# BMS.net
KiCad netlist of a schematic drawn in EAGLE
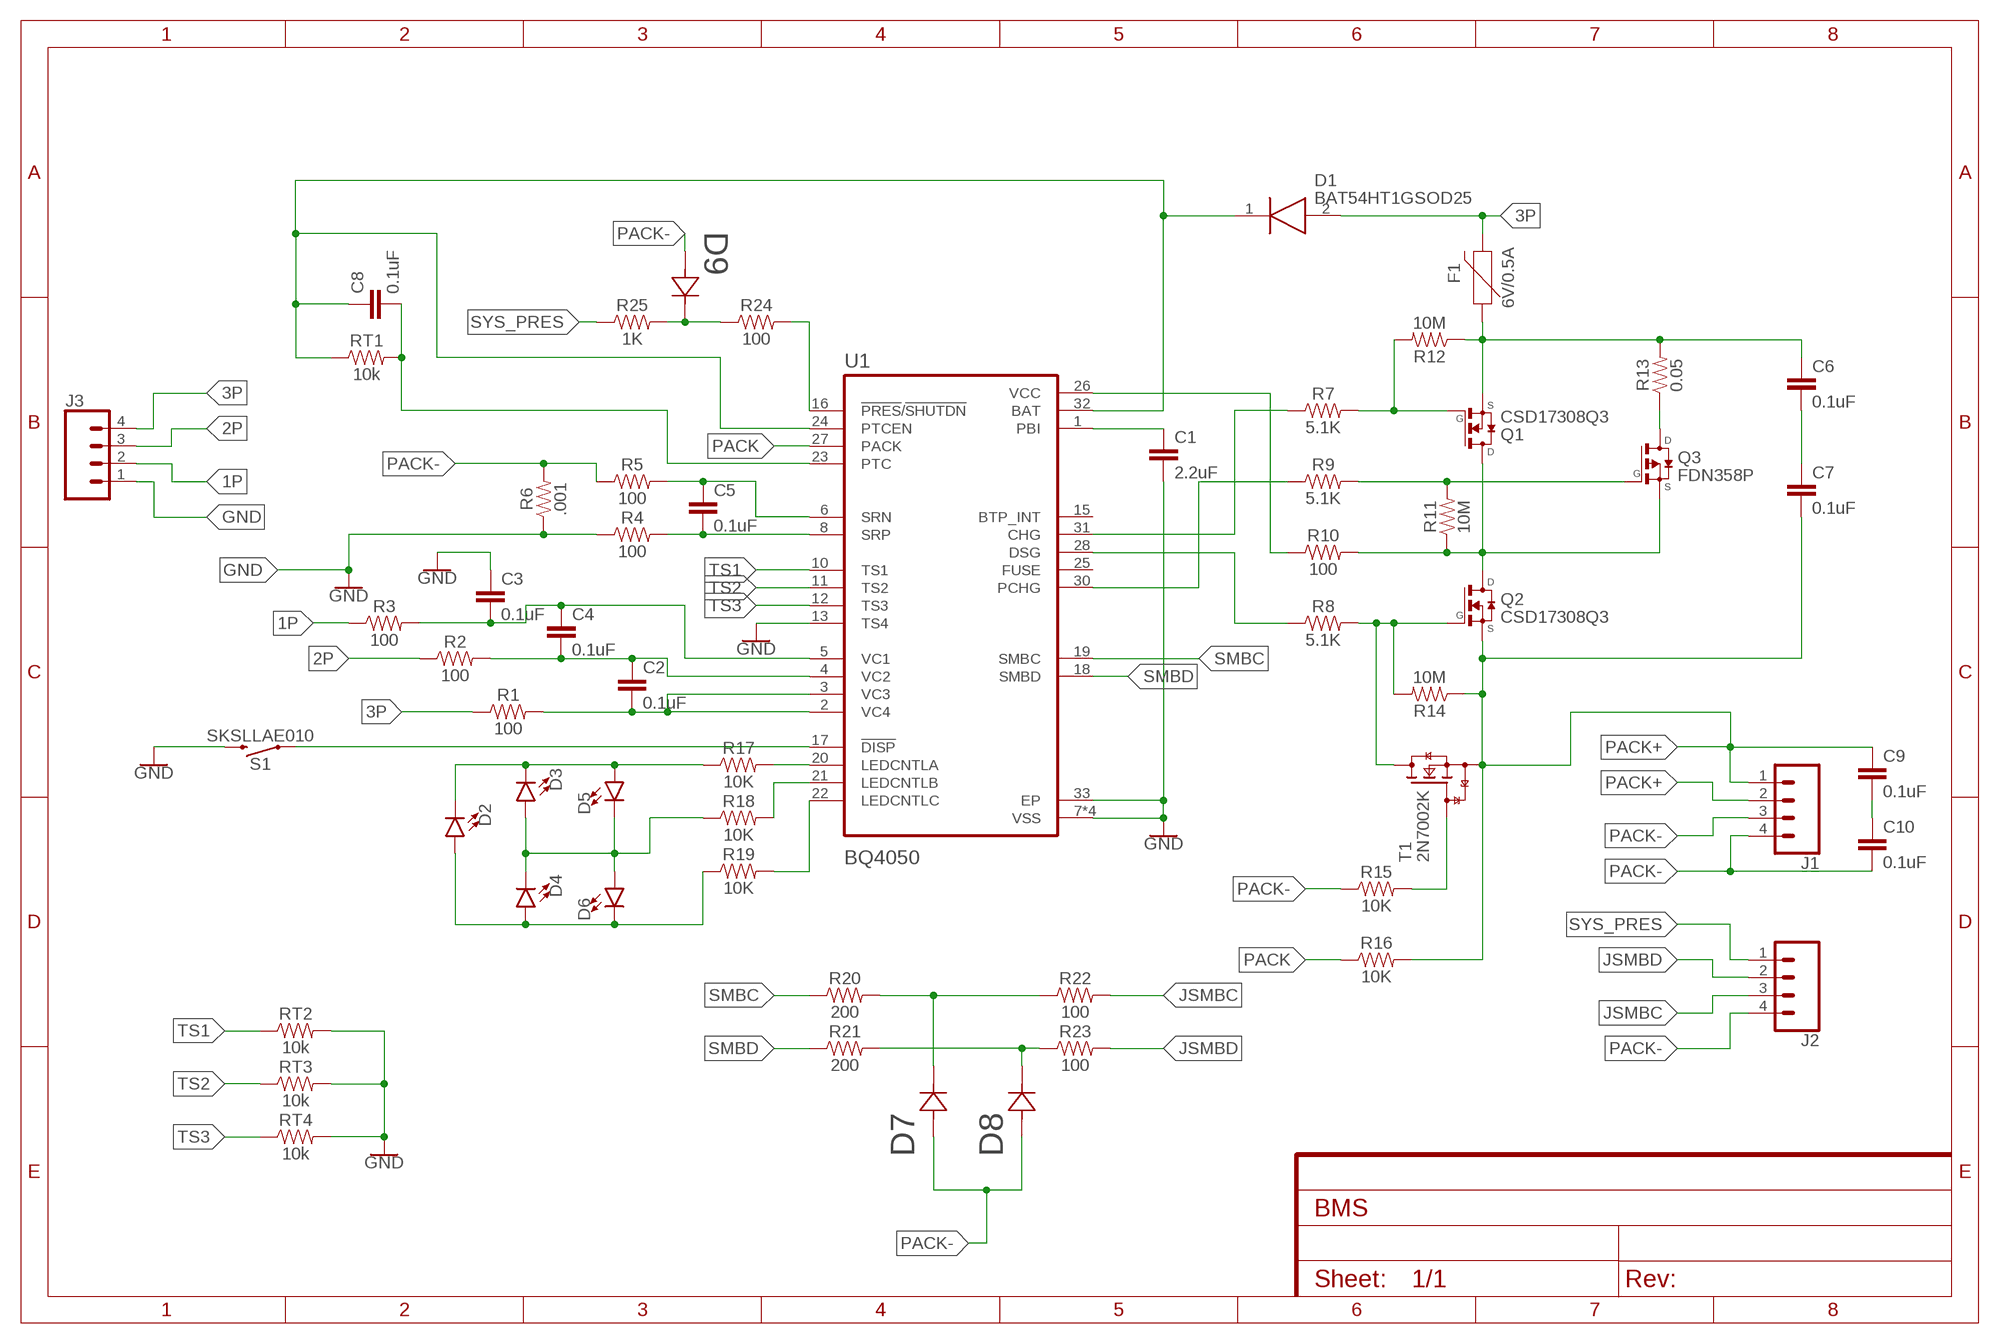
[diagram p0: schematic, sheet 1]

(export (version "E")
  (design (tool "Eeschema 10.0.6"))
  (components
    (comp (ref "C1")
      (value "2.2uF")
      (footprint "eagle-import:0402-CAP")
      (libsource (lib "eagle-import") (part "2.2UF-CERCAP-07888"))
    )
    (comp (ref "C2")
      (value "0.1uF")
      (footprint "eagle-import:0402")
      (libsource (lib "eagle-import") (part "0.1UF-0402-16V-10%"))
    )
    (comp (ref "C3")
      (value "0.1uF")
      (footprint "eagle-import:0402")
      (libsource (lib "eagle-import") (part "0.1UF-0402-16V-10%"))
    )
    (comp (ref "C4")
      (value "0.1uF")
      (footprint "eagle-import:0402")
      (libsource (lib "eagle-import") (part "0.1UF-0402-16V-10%"))
    )
    (comp (ref "C5")
      (value "0.1uF")
      (footprint "eagle-import:0402")
      (libsource (lib "eagle-import") (part "0.1UF-0402-16V-10%"))
    )
    (comp (ref "C6")
      (value "0.1uF")
      (footprint "eagle-import:0402")
      (libsource (lib "eagle-import") (part "0.1UF-0402-16V-10%"))
    )
    (comp (ref "C7")
      (value "0.1uF")
      (footprint "eagle-import:0402")
      (libsource (lib "eagle-import") (part "0.1UF-0402-16V-10%"))
    )
    (comp (ref "C8")
      (value "0.1uF")
      (footprint "eagle-import:0402")
      (libsource (lib "eagle-import") (part "0.1UF-0402-16V-10%"))
    )
    (comp (ref "C9")
      (value "0.1uF")
      (footprint "eagle-import:0402")
      (libsource (lib "eagle-import") (part "0.1UF-0402-16V-10%"))
    )
    (comp (ref "C10")
      (value "0.1uF")
      (footprint "eagle-import:0402")
      (libsource (lib "eagle-import") (part "0.1UF-0402-16V-10%"))
    )
    (comp (ref "D1")
      (value "BAT54HT1GSOD25")
      (footprint "eagle-import:SOD2512X100")
      (libsource (lib "eagle-import") (part "BAT54HT1GSOD25"))
    )
    (comp (ref "D2")
      (value "LTW-S272TLA-1175391")
      (footprint "eagle-import:LTW-S272TLA-1175391")
      (libsource (lib "eagle-import") (part "LTW-S272TLA-1175391"))
    )
    (comp (ref "D3")
      (value "LTW-S272TLA-1175391")
      (footprint "eagle-import:LTW-S272TLA-1175391")
      (libsource (lib "eagle-import") (part "LTW-S272TLA-1175391"))
    )
    (comp (ref "D4")
      (value "LTW-S272TLA-1175391")
      (footprint "eagle-import:LTW-S272TLA-1175391")
      (libsource (lib "eagle-import") (part "LTW-S272TLA-1175391"))
    )
    (comp (ref "D5")
      (value "LTW-S272TLA-1175391")
      (footprint "eagle-import:LTW-S272TLA-1175391")
      (libsource (lib "eagle-import") (part "LTW-S272TLA-1175391"))
    )
    (comp (ref "D6")
      (value "LTW-S272TLA-1175391")
      (footprint "eagle-import:LTW-S272TLA-1175391")
      (libsource (lib "eagle-import") (part "LTW-S272TLA-1175391"))
    )
    (comp (ref "D7")
      (value "D7")
      (footprint "eagle-import:SODFL2513X100")
      (libsource (lib "eagle-import") (part "MM3Z5V6ST1G"))
    )
    (comp (ref "D8")
      (value "D8")
      (footprint "eagle-import:SODFL2513X100")
      (libsource (lib "eagle-import") (part "MM3Z5V6ST1G"))
    )
    (comp (ref "D9")
      (value "D9")
      (footprint "eagle-import:SODFL2513X100")
      (libsource (lib "eagle-import") (part "MM3Z5V6ST1G"))
    )
    (comp (ref "F1")
      (value "6V/0.5A")
      (footprint "eagle-import:1206")
      (libsource (lib "eagle-import") (part "PPTC_HALF-AMP"))
    )
    (comp (ref "J1")
      (value "CONN_041.3HOLE")
      (footprint "eagle-import:1X04_1.3HOLE")
      (libsource (lib "eagle-import") (part "CONN_041.3HOLE"))
    )
    (comp (ref "J2")
      (value "CONN_041.3HOLE")
      (footprint "eagle-import:1X04_1.3HOLE")
      (libsource (lib "eagle-import") (part "CONN_041.3HOLE"))
    )
    (comp (ref "J3")
      (value "CONN_041X04_NO_SILK")
      (footprint "eagle-import:1X04_NO_SILK")
      (libsource (lib "eagle-import") (part "CONN_041X04_NO_SILK"))
    )
    (comp (ref "Q1")
      (value "CSD17308Q3")
      (footprint "eagle-import:SON8-Q3")
      (fields (field (name "DIGI-KEY_PART_NUMBER") "296-27210-1-ND") (field (name "MF") "Texas Instruments"))
      (libsource (lib "eagle-import") (part "CSD17308Q3"))
    )
    (comp (ref "Q2")
      (value "CSD17308Q3")
      (footprint "eagle-import:SON8-Q3")
      (fields (field (name "DIGI-KEY_PART_NUMBER") "296-27210-1-ND") (field (name "MF") "Texas Instruments"))
      (libsource (lib "eagle-import") (part "CSD17308Q3"))
    )
    (comp (ref "Q3")
      (value "FDN358P")
      (footprint "eagle-import:SSOT-3")
      (fields (field (name "DIGI-KEY_PART_NUMBER") "FDN358PCT-ND") (field (name "MF") "ON Semiconductor"))
      (libsource (lib "eagle-import") (part "FDN358P"))
    )
    (comp (ref "R1")
      (value "100")
      (footprint "eagle-import:0402")
      (libsource (lib "eagle-import") (part "100KOHM-0402-1/16W-1%"))
    )
    (comp (ref "R2")
      (value "100")
      (footprint "eagle-import:0402")
      (libsource (lib "eagle-import") (part "100KOHM-0402-1/16W-1%"))
    )
    (comp (ref "R3")
      (value "100")
      (footprint "eagle-import:0402")
      (libsource (lib "eagle-import") (part "100KOHM-0402-1/16W-1%"))
    )
    (comp (ref "R4")
      (value "100")
      (footprint "eagle-import:0402")
      (libsource (lib "eagle-import") (part "100KOHM-0402-1/16W-1%"))
    )
    (comp (ref "R5")
      (value "100")
      (footprint "eagle-import:0402")
      (libsource (lib "eagle-import") (part "100KOHM-0402-1/16W-1%"))
    )
    (comp (ref "R6")
      (value ".001")
      (footprint "eagle-import:RESC3015X65")
      (libsource (lib "eagle-import") (part "RNC18AQ00R001FE"))
    )
    (comp (ref "R7")
      (value "5.1K")
      (footprint "eagle-import:0402")
      (libsource (lib "eagle-import") (part "100KOHM-0402-1/16W-1%"))
    )
    (comp (ref "R8")
      (value "5.1K")
      (footprint "eagle-import:0402")
      (libsource (lib "eagle-import") (part "100KOHM-0402-1/16W-1%"))
    )
    (comp (ref "R9")
      (value "5.1K")
      (footprint "eagle-import:0402")
      (libsource (lib "eagle-import") (part "100KOHM-0402-1/16W-1%"))
    )
    (comp (ref "R10")
      (value "100")
      (footprint "eagle-import:0402")
      (libsource (lib "eagle-import") (part "100KOHM-0402-1/16W-1%"))
    )
    (comp (ref "R11")
      (value "10M")
      (footprint "eagle-import:0402")
      (libsource (lib "eagle-import") (part "100KOHM-0402-1/16W-1%"))
    )
    (comp (ref "R12")
      (value "10M")
      (footprint "eagle-import:0402")
      (libsource (lib "eagle-import") (part "100KOHM-0402-1/16W-1%"))
    )
    (comp (ref "R13")
      (value "0.05")
      (footprint "eagle-import:2512")
      (libsource (lib "eagle-import") (part "0.05OHM-2512-3W-1%"))
    )
    (comp (ref "R14")
      (value "10M")
      (footprint "eagle-import:0402")
      (libsource (lib "eagle-import") (part "100KOHM-0402-1/16W-1%"))
    )
    (comp (ref "R15")
      (value "10K")
      (footprint "eagle-import:0402")
      (libsource (lib "eagle-import") (part "100KOHM-0402-1/16W-1%"))
    )
    (comp (ref "R16")
      (value "10K")
      (footprint "eagle-import:0402")
      (libsource (lib "eagle-import") (part "100KOHM-0402-1/16W-1%"))
    )
    (comp (ref "R17")
      (value "10K")
      (footprint "eagle-import:0402")
      (libsource (lib "eagle-import") (part "100KOHM-0402-1/16W-1%"))
    )
    (comp (ref "R18")
      (value "10K")
      (footprint "eagle-import:0402")
      (libsource (lib "eagle-import") (part "100KOHM-0402-1/16W-1%"))
    )
    (comp (ref "R19")
      (value "10K")
      (footprint "eagle-import:0402")
      (libsource (lib "eagle-import") (part "100KOHM-0402-1/16W-1%"))
    )
    (comp (ref "R20")
      (value "200")
      (footprint "eagle-import:0402")
      (libsource (lib "eagle-import") (part "100KOHM-0402-1/16W-1%"))
    )
    (comp (ref "R21")
      (value "200")
      (footprint "eagle-import:0402")
      (libsource (lib "eagle-import") (part "100KOHM-0402-1/16W-1%"))
    )
    (comp (ref "R22")
      (value "100")
      (footprint "eagle-import:0402")
      (libsource (lib "eagle-import") (part "100KOHM-0402-1/16W-1%"))
    )
    (comp (ref "R23")
      (value "100")
      (footprint "eagle-import:0402")
      (libsource (lib "eagle-import") (part "100KOHM-0402-1/16W-1%"))
    )
    (comp (ref "R24")
      (value "100")
      (footprint "eagle-import:0402")
      (libsource (lib "eagle-import") (part "100KOHM-0402-1/16W-1%"))
    )
    (comp (ref "R25")
      (value "1K")
      (footprint "eagle-import:0402")
      (libsource (lib "eagle-import") (part "100KOHM-0402-1/16W-1%"))
    )
    (comp (ref "RT1")
      (value "10k")
      (footprint "eagle-import:1206")
      (libsource (lib "eagle-import") (part "TFPT1206L1002FM1206"))
    )
    (comp (ref "RT2")
      (value "10k")
      (footprint "eagle-import:NTC-RESISTOR")
      (libsource (lib "eagle-import") (part "NTCLE100E3"))
    )
    (comp (ref "RT3")
      (value "10k")
      (footprint "eagle-import:NTC-RESISTOR")
      (libsource (lib "eagle-import") (part "NTCLE100E3"))
    )
    (comp (ref "RT4")
      (value "10k")
      (footprint "eagle-import:NTC-RESISTOR")
      (libsource (lib "eagle-import") (part "NTCLE100E3"))
    )
    (comp (ref "S1")
      (value "SKSLLAE010")
      (footprint "eagle-import:SWITCH")
      (libsource (lib "eagle-import") (part "SKSLLAE010"))
    )
    (comp (ref "T1")
      (value "2N7002K")
      (footprint "eagle-import:SOT23")
      (fields (field (name "DIGI-KEY_PART_NUMBER") "2N7002KCT-ND") (field (name "MF") "ON Semiconductor"))
      (libsource (lib "eagle-import") (part "2N7002K"))
    )
    (comp (ref "U1")
      (value "BQ4050")
      (footprint "eagle-import:QFN40P400X400X100-33T140")
      (libsource (lib "eagle-import") (part "BQ4050RSMTBQ4050"))
    )
  )
  (nets
    (net (code "1") (name "1P") (class "Default")
      (node (ref "J3") (pin "2") (pinfunction "2_2") (pintype "passive"))
      (node (ref "R3") (pin "1") (pinfunction "1_1") (pintype "passive"))
    )
    (net (code "2") (name "2P") (class "Default")
      (node (ref "J3") (pin "3") (pinfunction "3_3") (pintype "passive"))
      (node (ref "R2") (pin "1") (pinfunction "1_1") (pintype "passive"))
    )
    (net (code "3") (name "3P") (class "Default")
      (node (ref "D1") (pin "2") (pinfunction "A_2") (pintype "bidirectional"))
      (node (ref "F1") (pin "2") (pinfunction "2_2") (pintype "bidirectional"))
      (node (ref "J3") (pin "4") (pinfunction "4_4") (pintype "passive"))
      (node (ref "R1") (pin "1") (pinfunction "1_1") (pintype "passive"))
    )
    (net (code "4") (name "GND") (class "Default")
      (node (ref "C1") (pin "2") (pinfunction "2_2") (pintype "passive"))
      (node (ref "C3") (pin "1") (pinfunction "1_1") (pintype "passive"))
      (node (ref "J3") (pin "1") (pinfunction "1_1") (pintype "passive"))
      (node (ref "R4") (pin "1") (pinfunction "1_1") (pintype "passive"))
      (node (ref "R6") (pin "1") (pinfunction "1_1") (pintype "passive"))
      (node (ref "RT2") (pin "2") (pinfunction "2_2") (pintype "passive"))
      (node (ref "RT3") (pin "2") (pinfunction "2_2") (pintype "passive"))
      (node (ref "RT4") (pin "2") (pinfunction "2_2") (pintype "passive"))
      (node (ref "S1") (pin "P$2") (pinfunction "2_P$2") (pintype "passive"))
      (node (ref "U1") (pin "13") (pinfunction "TS4_13") (pintype "input"))
      (node (ref "U1") (pin "14") (pinfunction "VSS_14") (pintype "power_in"))
      (node (ref "U1") (pin "29") (pinfunction "VSS_29") (pintype "power_in"))
      (node (ref "U1") (pin "33") (pinfunction "EP_33") (pintype "power_in"))
      (node (ref "U1") (pin "7") (pinfunction "VSS_7") (pintype "power_in"))
      (node (ref "U1") (pin "9") (pinfunction "VSS_9") (pintype "power_in"))
    )
    (net (code "5") (name "JSMBC") (class "Default")
      (node (ref "J2") (pin "3") (pinfunction "3_3") (pintype "passive"))
      (node (ref "R22") (pin "2") (pinfunction "2_2") (pintype "passive"))
    )
    (net (code "6") (name "JSMBD") (class "Default")
      (node (ref "J2") (pin "2") (pinfunction "2_2") (pintype "passive"))
      (node (ref "R23") (pin "2") (pinfunction "2_2") (pintype "passive"))
    )
    (net (code "7") (name "Net-(C6-Pad2)") (class "Default")
      (node (ref "C6") (pin "2") (pinfunction "2_2") (pintype "passive"))
      (node (ref "C7") (pin "1") (pinfunction "1_1") (pintype "passive"))
    )
    (net (code "8") (name "Net-(C10-Pad1)") (class "Default")
      (node (ref "C10") (pin "1") (pinfunction "1_1") (pintype "passive"))
      (node (ref "C9") (pin "2") (pinfunction "2_2") (pintype "passive"))
    )
    (net (code "9") (name "Net-(D1-K)") (class "Default")
      (node (ref "C8") (pin "1") (pinfunction "1_1") (pintype "passive"))
      (node (ref "D1") (pin "1") (pinfunction "K_1") (pintype "bidirectional"))
      (node (ref "RT1") (pin "1") (pinfunction "1_1") (pintype "passive"))
      (node (ref "U1") (pin "24") (pinfunction "PTCEN_24") (pintype "input"))
      (node (ref "U1") (pin "32") (pinfunction "BAT_32") (pintype "power_in"))
    )
    (net (code "10") (name "Net-(D2-A)") (class "Default")
      (node (ref "D2") (pin "P$2") (pinfunction "A_P$2") (pintype "passive"))
      (node (ref "D4") (pin "P$2") (pinfunction "A_P$2") (pintype "passive"))
      (node (ref "D6") (pin "P$1") (pinfunction "C_P$1") (pintype "passive"))
      (node (ref "R19") (pin "1") (pinfunction "1_1") (pintype "passive"))
    )
    (net (code "11") (name "Net-(D2-C)") (class "Default")
      (node (ref "D2") (pin "P$1") (pinfunction "C_P$1") (pintype "passive"))
      (node (ref "D3") (pin "P$1") (pinfunction "C_P$1") (pintype "passive"))
      (node (ref "D5") (pin "P$2") (pinfunction "A_P$2") (pintype "passive"))
      (node (ref "R17") (pin "1") (pinfunction "1_1") (pintype "passive"))
    )
    (net (code "12") (name "Net-(D3-A)") (class "Default")
      (node (ref "D3") (pin "P$2") (pinfunction "A_P$2") (pintype "passive"))
      (node (ref "D4") (pin "P$1") (pinfunction "C_P$1") (pintype "passive"))
      (node (ref "D5") (pin "P$1") (pinfunction "C_P$1") (pintype "passive"))
      (node (ref "D6") (pin "P$2") (pinfunction "A_P$2") (pintype "passive"))
      (node (ref "R18") (pin "1") (pinfunction "1_1") (pintype "passive"))
    )
    (net (code "13") (name "Net-(D7-Pad1)") (class "Default")
      (node (ref "D7") (pin "1") (pinfunction "1_1") (pintype "passive"))
      (node (ref "R20") (pin "2") (pinfunction "2_2") (pintype "passive"))
      (node (ref "R22") (pin "1") (pinfunction "1_1") (pintype "passive"))
    )
    (net (code "14") (name "Net-(D8-Pad1)") (class "Default")
      (node (ref "D8") (pin "1") (pinfunction "1_1") (pintype "passive"))
      (node (ref "R21") (pin "2") (pinfunction "2_2") (pintype "passive"))
      (node (ref "R23") (pin "1") (pinfunction "1_1") (pintype "passive"))
    )
    (net (code "15") (name "Net-(D9-Pad1)") (class "Default")
      (node (ref "D9") (pin "1") (pinfunction "1_1") (pintype "passive"))
      (node (ref "R24") (pin "1") (pinfunction "1_1") (pintype "passive"))
      (node (ref "R25") (pin "2") (pinfunction "2_2") (pintype "passive"))
    )
    (net (code "16") (name "Net-(Q1-G)") (class "Default")
      (node (ref "Q1") (pin "4") (pinfunction "G_4") (pintype "passive"))
      (node (ref "R12") (pin "2") (pinfunction "2_2") (pintype "passive"))
      (node (ref "R7") (pin "2") (pinfunction "2_2") (pintype "passive"))
    )
    (net (code "17") (name "Net-(Q2-G)") (class "Default")
      (node (ref "Q2") (pin "4") (pinfunction "G_4") (pintype "passive"))
      (node (ref "R14") (pin "2") (pinfunction "2_2") (pintype "passive"))
      (node (ref "R8") (pin "2") (pinfunction "2_2") (pintype "passive"))
      (node (ref "T1") (pin "3") (pinfunction "D_3") (pintype "passive"))
    )
    (net (code "18") (name "Net-(Q3-D)") (class "Default")
      (node (ref "Q3") (pin "3") (pinfunction "D_3") (pintype "passive"))
      (node (ref "R13") (pin "P$1") (pinfunction "1_P$1") (pintype "passive"))
    )
    (net (code "19") (name "Net-(Q3-G)") (class "Default")
      (node (ref "Q3") (pin "1") (pinfunction "G_1") (pintype "passive"))
      (node (ref "R11") (pin "2") (pinfunction "2_2") (pintype "passive"))
      (node (ref "R9") (pin "2") (pinfunction "2_2") (pintype "passive"))
    )
    (net (code "20") (name "Net-(Q3-S)") (class "Default")
      (node (ref "Q1") (pin "5") (pinfunction "D_5") (pintype "passive"))
      (node (ref "Q1") (pin "6") (pinfunction "D_6") (pintype "passive"))
      (node (ref "Q1") (pin "7") (pinfunction "D_7") (pintype "passive"))
      (node (ref "Q1") (pin "8") (pinfunction "D_8") (pintype "passive"))
      (node (ref "Q2") (pin "5") (pinfunction "D_5") (pintype "passive"))
      (node (ref "Q2") (pin "6") (pinfunction "D_6") (pintype "passive"))
      (node (ref "Q2") (pin "7") (pinfunction "D_7") (pintype "passive"))
      (node (ref "Q2") (pin "8") (pinfunction "D_8") (pintype "passive"))
      (node (ref "Q3") (pin "2") (pinfunction "S_2") (pintype "passive"))
      (node (ref "R10") (pin "2") (pinfunction "2_2") (pintype "passive"))
      (node (ref "R11") (pin "1") (pinfunction "1_1") (pintype "passive"))
    )
    (net (code "21") (name "Net-(R13-2)") (class "Default")
      (node (ref "C6") (pin "1") (pinfunction "1_1") (pintype "passive"))
      (node (ref "F1") (pin "1") (pinfunction "1_1") (pintype "bidirectional"))
      (node (ref "Q1") (pin "1") (pinfunction "S_1") (pintype "passive"))
      (node (ref "Q1") (pin "2") (pinfunction "S_2") (pintype "passive"))
      (node (ref "Q1") (pin "3") (pinfunction "S_3") (pintype "passive"))
      (node (ref "R12") (pin "1") (pinfunction "1_1") (pintype "passive"))
      (node (ref "R13") (pin "P$2") (pinfunction "2_P$2") (pintype "passive"))
    )
    (net (code "22") (name "Net-(S1-1)") (class "Default")
      (node (ref "S1") (pin "P$1") (pinfunction "1_P$1") (pintype "passive"))
      (node (ref "U1") (pin "17") (pinfunction "~{DISP}_17") (pintype "passive"))
    )
    (net (code "23") (name "Net-(T1-G)") (class "Default")
      (node (ref "R15") (pin "2") (pinfunction "2_2") (pintype "passive"))
      (node (ref "T1") (pin "1") (pinfunction "G_1") (pintype "passive"))
    )
    (net (code "24") (name "Net-(U1-CHG)") (class "Default")
      (node (ref "R7") (pin "1") (pinfunction "1_1") (pintype "passive"))
      (node (ref "U1") (pin "31") (pinfunction "CHG_31") (pintype "output"))
    )
    (net (code "25") (name "Net-(U1-DSG)") (class "Default")
      (node (ref "R8") (pin "1") (pinfunction "1_1") (pintype "passive"))
      (node (ref "U1") (pin "28") (pinfunction "DSG_28") (pintype "output"))
    )
    (net (code "26") (name "Net-(U1-LEDCNTLA)") (class "Default")
      (node (ref "R17") (pin "2") (pinfunction "2_2") (pintype "passive"))
      (node (ref "U1") (pin "20") (pinfunction "LEDCNTLA_20") (pintype "passive"))
    )
    (net (code "27") (name "Net-(U1-LEDCNTLB)") (class "Default")
      (node (ref "R18") (pin "2") (pinfunction "2_2") (pintype "passive"))
      (node (ref "U1") (pin "21") (pinfunction "LEDCNTLB_21") (pintype "passive"))
    )
    (net (code "28") (name "Net-(U1-LEDCNTLC)") (class "Default")
      (node (ref "R19") (pin "2") (pinfunction "2_2") (pintype "passive"))
      (node (ref "U1") (pin "22") (pinfunction "LEDCNTLC_22") (pintype "passive"))
    )
    (net (code "29") (name "Net-(U1-PBI)") (class "Default")
      (node (ref "C1") (pin "1") (pinfunction "1_1") (pintype "passive"))
      (node (ref "U1") (pin "1") (pinfunction "PBI_1") (pintype "power_in"))
    )
    (net (code "30") (name "Net-(U1-PCHG)") (class "Default")
      (node (ref "R9") (pin "1") (pinfunction "1_1") (pintype "passive"))
      (node (ref "U1") (pin "30") (pinfunction "PCHG_30") (pintype "output"))
    )
    (net (code "31") (name "Net-(U1-PTC)") (class "Default")
      (node (ref "C8") (pin "2") (pinfunction "2_2") (pintype "passive"))
      (node (ref "RT1") (pin "2") (pinfunction "2_2") (pintype "passive"))
      (node (ref "U1") (pin "23") (pinfunction "PTC_23") (pintype "input"))
    )
    (net (code "32") (name "Net-(U1-SRN)") (class "Default")
      (node (ref "C5") (pin "1") (pinfunction "1_1") (pintype "passive"))
      (node (ref "R5") (pin "2") (pinfunction "2_2") (pintype "passive"))
      (node (ref "U1") (pin "6") (pinfunction "SRN_6") (pintype "input"))
    )
    (net (code "33") (name "Net-(U1-SRP)") (class "Default")
      (node (ref "C5") (pin "2") (pinfunction "2_2") (pintype "passive"))
      (node (ref "R4") (pin "2") (pinfunction "2_2") (pintype "passive"))
      (node (ref "U1") (pin "8") (pinfunction "SRP_8") (pintype "input"))
    )
    (net (code "34") (name "Net-(U1-VC1)") (class "Default")
      (node (ref "C3") (pin "2") (pinfunction "2_2") (pintype "passive"))
      (node (ref "C4") (pin "1") (pinfunction "1_1") (pintype "passive"))
      (node (ref "R3") (pin "2") (pinfunction "2_2") (pintype "passive"))
      (node (ref "U1") (pin "5") (pinfunction "VC1_5") (pintype "input"))
    )
    (net (code "35") (name "Net-(U1-VC2)") (class "Default")
      (node (ref "C2") (pin "1") (pinfunction "1_1") (pintype "passive"))
      (node (ref "C4") (pin "2") (pinfunction "2_2") (pintype "passive"))
      (node (ref "R2") (pin "2") (pinfunction "2_2") (pintype "passive"))
      (node (ref "U1") (pin "4") (pinfunction "VC2_4") (pintype "input"))
    )
    (net (code "36") (name "Net-(U1-VC3)") (class "Default")
      (node (ref "C2") (pin "2") (pinfunction "2_2") (pintype "passive"))
      (node (ref "R1") (pin "2") (pinfunction "2_2") (pintype "passive"))
      (node (ref "U1") (pin "2") (pinfunction "VC4_2") (pintype "input"))
      (node (ref "U1") (pin "3") (pinfunction "VC3_3") (pintype "input"))
    )
    (net (code "37") (name "Net-(U1-VCC)") (class "Default")
      (node (ref "R10") (pin "1") (pinfunction "1_1") (pintype "passive"))
      (node (ref "U1") (pin "26") (pinfunction "VCC_26") (pintype "power_in"))
    )
    (net (code "38") (name "Net-(U1-~{PRES}{slash}~{SHUTDN})") (class "Default")
      (node (ref "R24") (pin "2") (pinfunction "2_2") (pintype "passive"))
      (node (ref "U1") (pin "16") (pinfunction "~{PRES}/~{SHUTDN}_16") (pintype "input"))
    )
    (net (code "39") (name "PACK") (class "Default")
      (node (ref "R16") (pin "1") (pinfunction "1_1") (pintype "passive"))
      (node (ref "U1") (pin "27") (pinfunction "PACK_27") (pintype "input"))
    )
    (net (code "40") (name "PACK+") (class "Default")
      (node (ref "C7") (pin "2") (pinfunction "2_2") (pintype "passive"))
      (node (ref "C9") (pin "1") (pinfunction "1_1") (pintype "passive"))
      (node (ref "J1") (pin "1") (pinfunction "1_1") (pintype "passive"))
      (node (ref "J1") (pin "2") (pinfunction "2_2") (pintype "passive"))
      (node (ref "Q2") (pin "1") (pinfunction "S_1") (pintype "passive"))
      (node (ref "Q2") (pin "2") (pinfunction "S_2") (pintype "passive"))
      (node (ref "Q2") (pin "3") (pinfunction "S_3") (pintype "passive"))
      (node (ref "R14") (pin "1") (pinfunction "1_1") (pintype "passive"))
      (node (ref "R16") (pin "2") (pinfunction "2_2") (pintype "passive"))
      (node (ref "T1") (pin "2") (pinfunction "S_2") (pintype "passive"))
    )
    (net (code "41") (name "PACK-") (class "Default")
      (node (ref "C10") (pin "2") (pinfunction "2_2") (pintype "passive"))
      (node (ref "D7") (pin "2") (pinfunction "2_2") (pintype "passive"))
      (node (ref "D8") (pin "2") (pinfunction "2_2") (pintype "passive"))
      (node (ref "D9") (pin "2") (pinfunction "2_2") (pintype "passive"))
      (node (ref "J1") (pin "3") (pinfunction "3_3") (pintype "passive"))
      (node (ref "J1") (pin "4") (pinfunction "4_4") (pintype "passive"))
      (node (ref "J2") (pin "4") (pinfunction "4_4") (pintype "passive"))
      (node (ref "R15") (pin "1") (pinfunction "1_1") (pintype "passive"))
      (node (ref "R5") (pin "1") (pinfunction "1_1") (pintype "passive"))
      (node (ref "R6") (pin "2") (pinfunction "2_2") (pintype "passive"))
    )
    (net (code "42") (name "SMBC") (class "Default")
      (node (ref "R20") (pin "1") (pinfunction "1_1") (pintype "passive"))
      (node (ref "U1") (pin "19") (pinfunction "SMBC_19") (pintype "bidirectional"))
    )
    (net (code "43") (name "SMBD") (class "Default")
      (node (ref "R21") (pin "1") (pinfunction "1_1") (pintype "passive"))
      (node (ref "U1") (pin "18") (pinfunction "SMBD_18") (pintype "bidirectional"))
    )
    (net (code "44") (name "SYS_PRES") (class "Default")
      (node (ref "J2") (pin "1") (pinfunction "1_1") (pintype "passive"))
      (node (ref "R25") (pin "1") (pinfunction "1_1") (pintype "passive"))
    )
    (net (code "45") (name "TS1") (class "Default")
      (node (ref "RT2") (pin "1") (pinfunction "1_1") (pintype "passive"))
      (node (ref "U1") (pin "10") (pinfunction "TS1_10") (pintype "input"))
    )
    (net (code "46") (name "TS2") (class "Default")
      (node (ref "RT3") (pin "1") (pinfunction "1_1") (pintype "passive"))
      (node (ref "U1") (pin "11") (pinfunction "TS2_11") (pintype "input"))
    )
    (net (code "47") (name "TS3") (class "Default")
      (node (ref "RT4") (pin "1") (pinfunction "1_1") (pintype "passive"))
      (node (ref "U1") (pin "12") (pinfunction "TS3_12") (pintype "input"))
    )
    (net (code "48") (name "unconnected-(U1-BTP_INT-Pad15)") (class "Default")
      (node (ref "U1") (pin "15") (pinfunction "BTP_INT_15") (pintype "output"))
    )
    (net (code "49") (name "unconnected-(U1-FUSE-Pad25)") (class "Default")
      (node (ref "U1") (pin "25") (pinfunction "FUSE_25") (pintype "output"))
    )
  )
)
